# Camera_Shield_Headers.net
KiCad netlist of a schematic drawn in Altium Designer
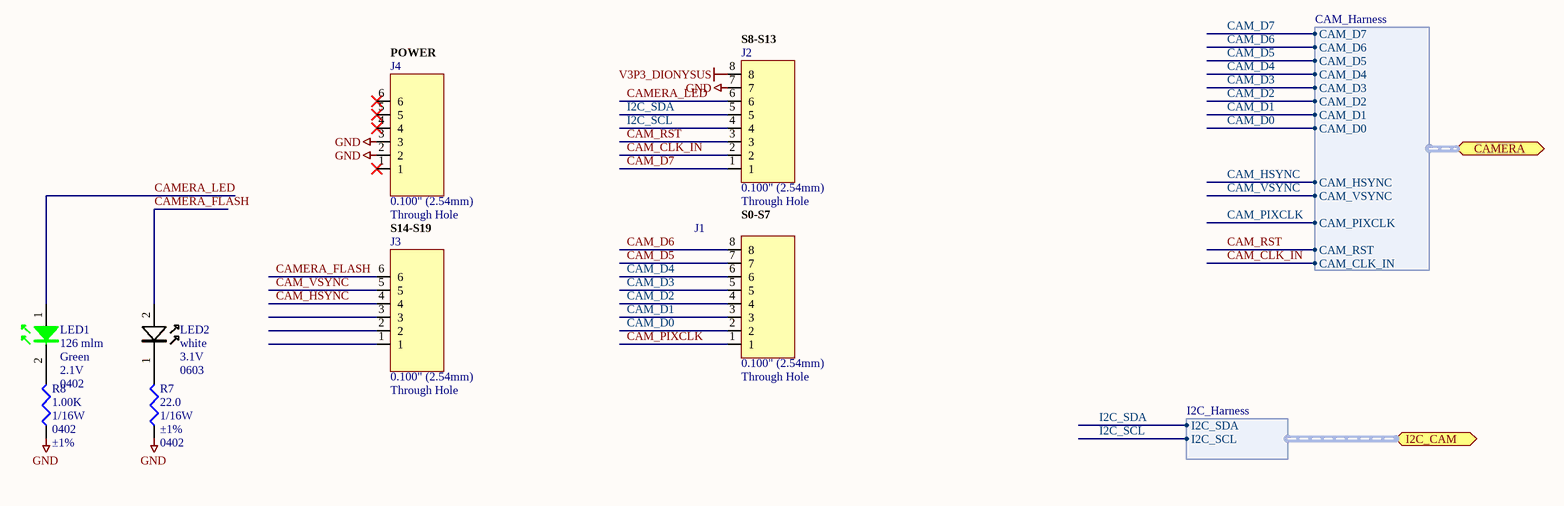
[diagram p0: Camera_Shield_Headers.SchDoc]

(export (version "E")
  (design (tool "Eeschema 10.0.6"))
  (components
    (comp (ref "J1")
      (value "J_HDR1X8_THRHOLE_VERT")
      (footprint "HDR_1X8")
      (description "CONN HEADER .100\" 12POS TIN PCB")
      (fields
        (field (name "MANUFACTURER") "Samtec")
        (field (name "MANUFACTURER PART NUMBER") "TS-108-T-A")
        (field (name "PITCH") "0.100\" (2.54mm)")
        (field (name "MOUNTING TYPE") "Through Hole")
      )
      (libsource (lib "Main Library") (part "J_HDR1X8_THRHOLE_VERT"))
    )
    (comp (ref "J2")
      (value "J_HDR1X8_THRHOLE_VERT")
      (footprint "HDR_1X8")
      (description "CONN HEADER .100\" 12POS TIN PCB")
      (fields
        (field (name "MANUFACTURER") "Samtec")
        (field (name "MANUFACTURER PART NUMBER") "TS-108-T-A")
        (field (name "PITCH") "0.100\" (2.54mm)")
        (field (name "MOUNTING TYPE") "Through Hole")
      )
      (libsource (lib "Main Library") (part "J_HDR1X8_THRHOLE_VERT"))
    )
    (comp (ref "J3")
      (value "J_HDR1X6_THRHOLE_VERT")
      (footprint "HDR_1X6")
      (description "CONN HEADER .100\" 12POS TIN PCB")
      (fields
        (field (name "MANUFACTURER") "Samtec")
        (field (name "MANUFACTURER PART NUMBER") "TSW-106-07-T-S")
        (field (name "PITCH") "0.100\" (2.54mm)")
        (field (name "MOUNTING TYPE") "Through Hole")
      )
      (libsource (lib "Main Library") (part "J_HDR1X6_THRHOLE_VERT"))
    )
    (comp (ref "J4")
      (value "J_HDR1X6_THRHOLE_VERT")
      (footprint "HDR_1X6")
      (description "CONN HEADER .100\" 12POS TIN PCB")
      (fields
        (field (name "MANUFACTURER") "Samtec")
        (field (name "MANUFACTURER PART NUMBER") "TSW-106-07-T-S")
        (field (name "PITCH") "0.100\" (2.54mm)")
        (field (name "MOUNTING TYPE") "Through Hole")
      )
      (libsource (lib "Main Library") (part "J_HDR1X6_THRHOLE_VERT"))
    )
    (comp (ref "LED1")
      (value "LED_GRN_0402")
      (footprint "DIOM1005X07L_GREEN")
      (description "LED 1X0.5MM 570NM GN WTR CLR SMD")
      (fields
        (field (name "MANUFACTURER") "Kingbright Corp")
        (field (name "MANUFACTURER PART NUMBER") "APHHS1005CGCK")
        (field (name "LUMINOUS FLUX @ CURRENT - TEST") "126 mlm")
        (field (name "COLOR") "Green")
        (field (name "VOLTAGE - FORWARD (VF) TYP") "2.1V")
        (field (name "PACKAGE / CASE") "0402")
      )
      (libsource (lib "Main Library") (part "LED_GRN_0402"))
    )
    (comp (ref "LED2")
      (value "LED_WHITE_0603")
      (footprint "DIOM0603")
      (description "LED SMARTLED WHITE DIFF 0603 SMD")
      (fields
        (field (name "MANUFACTURER") "OSRAM Opto Semiconductors Inc")
        (field (name "MANUFACTURER PART NUMBER") "LW L283-P2R1-3K8L-1-Z")
        (field (name "COLOR") "white")
        (field (name "VOLTAGE - FORWARD (VF) TYP") "3.1V")
        (field (name "PACKAGE / CASE") "0603")
      )
      (libsource (lib "Main Library") (part "LED_WHITE_0603"))
    )
    (comp (ref "R7")
      (value "R_0402_22.0")
      (footprint "ERA-0402")
      (description "RES 22.0 OHM 1/16W 1% 0402 SMD")
      (fields
        (field (name "MANUFACTURER") "Vishay Dale")
        (field (name "MANUFACTURER PART NUMBER") "CRCW040222R0FKED")
        (field (name "RESISTANCE IN OHMS") "22.0")
        (field (name "POWER (WATTS)") "1/16W")
        (field (name "TOLERANCE") "±1%")
        (field (name "CASE") "0402")
      )
      (libsource (lib "Main LibraryX") (part "R_0402_22.0"))
    )
    (comp (ref "R8")
      (value "1.0k Ohms")
      (footprint "ERA-0402")
      (description "RES 1.00K OHM 1/16W 1% 0402 SMD")
      (fields
        (field (name "MANUFACTURER") "Yageo")
        (field (name "MANUFACTURER PART NUMBER") "RC0402FR-071KL")
        (field (name "RESISTANCE IN OHMS") "1.00K")
        (field (name "POWER (WATTS)") "1/16W")
        (field (name "CASE") "0402")
        (field (name "TOLERANCE") "±1%")
      )
      (libsource (lib "Main Library") (part "R_0402_1.0K"))
    )
  )
  (nets
    (net (code "3") (name "/CAMERA_FLASH") (class "Default")
      (node (ref "J3") (pin "6") (pinfunction "6_6") (pintype "passive"))
      (node (ref "LED2") (pin "2") (pinfunction "2_2") (pintype "passive"))
    )
    (net (code "4") (name "/CAMERA_LED") (class "Default")
      (node (ref "J2") (pin "6") (pinfunction "6_6") (pintype "passive"))
      (node (ref "LED1") (pin "1") (pinfunction "1_1") (pintype "passive"))
    )
    (net (code "5") (name "/CAM_CLK_IN") (class "Default")
      (node (ref "J2") (pin "2") (pinfunction "2_2") (pintype "passive"))
    )
    (net (code "6") (name "/CAM_D0") (class "Default")
      (node (ref "J1") (pin "2") (pinfunction "2_2") (pintype "passive"))
    )
    (net (code "7") (name "/CAM_D1") (class "Default")
      (node (ref "J1") (pin "3") (pinfunction "3_3") (pintype "passive"))
    )
    (net (code "8") (name "/CAM_D2") (class "Default")
      (node (ref "J1") (pin "4") (pinfunction "4_4") (pintype "passive"))
    )
    (net (code "9") (name "/CAM_D3") (class "Default")
      (node (ref "J1") (pin "5") (pinfunction "5_5") (pintype "passive"))
    )
    (net (code "10") (name "/CAM_D4") (class "Default")
      (node (ref "J1") (pin "6") (pinfunction "6_6") (pintype "passive"))
    )
    (net (code "11") (name "/CAM_D5") (class "Default")
      (node (ref "J1") (pin "7") (pinfunction "7_7") (pintype "passive"))
    )
    (net (code "12") (name "/CAM_D6") (class "Default")
      (node (ref "J1") (pin "8") (pinfunction "8_8") (pintype "passive"))
    )
    (net (code "13") (name "/CAM_D7") (class "Default")
      (node (ref "J2") (pin "1") (pinfunction "1_1") (pintype "passive"))
    )
    (net (code "14") (name "/CAM_HSYNC") (class "Default")
      (node (ref "J3") (pin "4") (pinfunction "4_4") (pintype "passive"))
    )
    (net (code "15") (name "/CAM_PIXCLK") (class "Default")
      (node (ref "J1") (pin "1") (pinfunction "1_1") (pintype "passive"))
    )
    (net (code "16") (name "/CAM_RST") (class "Default")
      (node (ref "J2") (pin "3") (pinfunction "3_3") (pintype "passive"))
    )
    (net (code "17") (name "/CAM_VSYNC") (class "Default")
      (node (ref "J3") (pin "5") (pinfunction "5_5") (pintype "passive"))
    )
    (net (code "18") (name "/I2C_SCL") (class "Default")
      (node (ref "J2") (pin "4") (pinfunction "4_4") (pintype "passive"))
    )
    (net (code "19") (name "/I2C_SDA") (class "Default")
      (node (ref "J2") (pin "5") (pinfunction "5_5") (pintype "passive"))
    )
    (net (code "22") (name "GND") (class "Default")
      (node (ref "J2") (pin "7") (pinfunction "7_7") (pintype "passive"))
      (node (ref "J4") (pin "2") (pinfunction "2_2") (pintype "passive"))
      (node (ref "J4") (pin "3") (pinfunction "3_3") (pintype "passive"))
      (node (ref "R7") (pin "2") (pinfunction "2_2") (pintype "passive"))
      (node (ref "R8") (pin "2") (pinfunction "2_2") (pintype "passive"))
    )
    (net (code "23") (name "Net-(LED1-Pad2)") (class "Default")
      (node (ref "LED1") (pin "2") (pinfunction "2_2") (pintype "passive"))
      (node (ref "R8") (pin "1") (pinfunction "1_1") (pintype "passive"))
    )
    (net (code "24") (name "Net-(LED2-Pad1)") (class "Default")
      (node (ref "LED2") (pin "1") (pinfunction "1_1") (pintype "passive"))
      (node (ref "R7") (pin "1") (pinfunction "1_1") (pintype "passive"))
    )
    (net (code "25") (name "V3P3_DIONYSUS") (class "Default")
      (node (ref "J2") (pin "8") (pinfunction "8_8") (pintype "passive"))
    )
    (net (code "26") (name "unconnected-(J3-Pad1)") (class "Default")
      (node (ref "J3") (pin "1") (pinfunction "1_1") (pintype "passive"))
    )
    (net (code "27") (name "unconnected-(J3-Pad2)") (class "Default")
      (node (ref "J3") (pin "2") (pinfunction "2_2") (pintype "passive"))
    )
    (net (code "28") (name "unconnected-(J3-Pad3)") (class "Default")
      (node (ref "J3") (pin "3") (pinfunction "3_3") (pintype "passive"))
    )
    (net (code "29") (name "unconnected-(J4-Pad1)") (class "Default")
      (node (ref "J4") (pin "1") (pinfunction "1_1") (pintype "passive+no_connect"))
    )
    (net (code "30") (name "unconnected-(J4-Pad4)") (class "Default")
      (node (ref "J4") (pin "4") (pinfunction "4_4") (pintype "passive+no_connect"))
    )
    (net (code "31") (name "unconnected-(J4-Pad5)") (class "Default")
      (node (ref "J4") (pin "5") (pinfunction "5_5") (pintype "passive+no_connect"))
    )
    (net (code "32") (name "unconnected-(J4-Pad6)") (class "Default")
      (node (ref "J4") (pin "6") (pinfunction "6_6") (pintype "passive+no_connect"))
    )
  )
)
